# pi_pcb.net
KiCad netlist of a schematic drawn in EAGLE
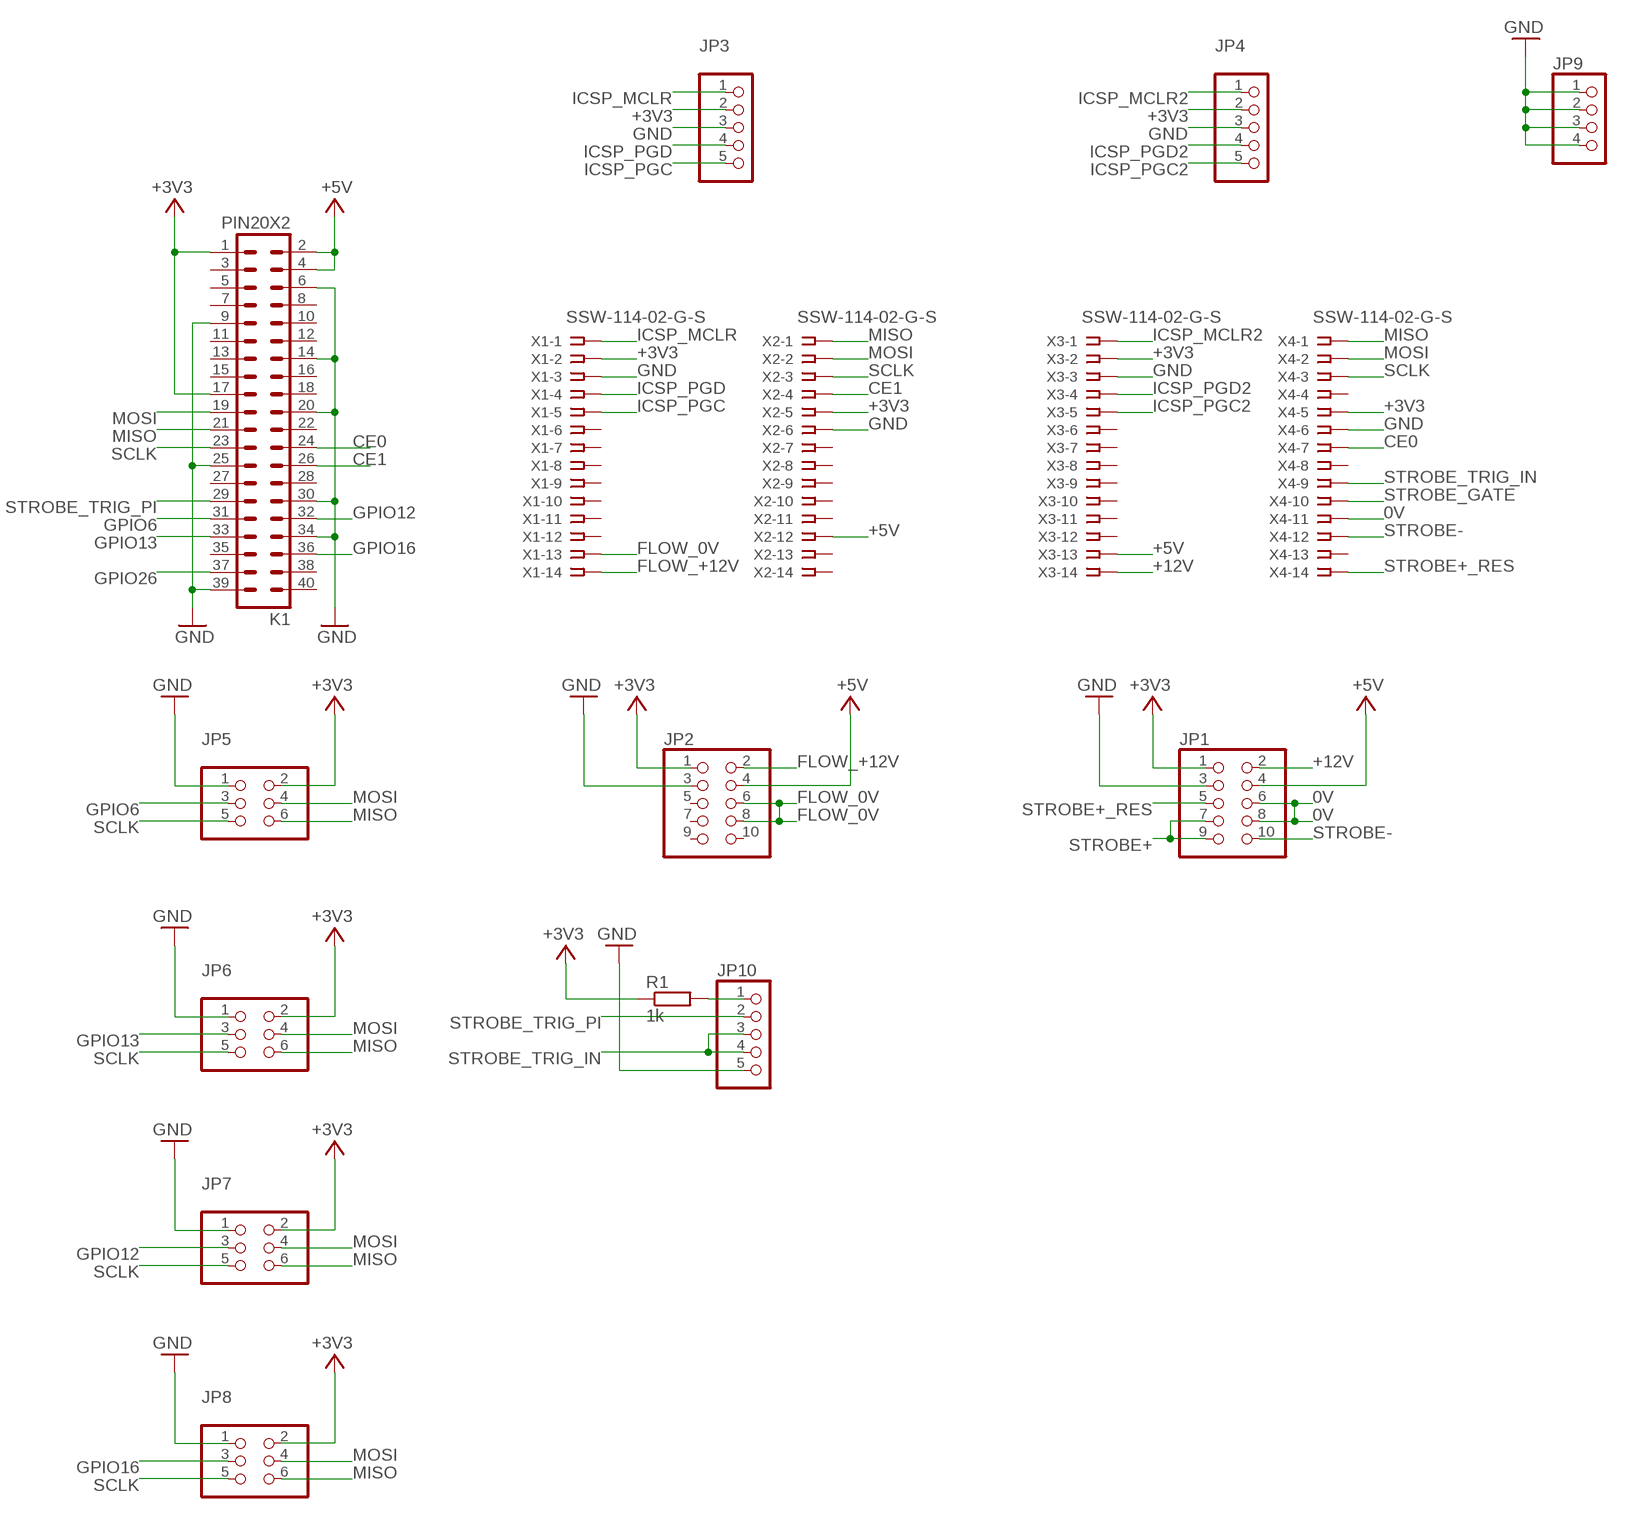
[diagram p0: schematic, sheet 1]

(export (version "E")
  (design (tool "Eeschema 10.0.6"))
  (components
    (comp (ref "JP1")
      (value "PINHD-2X5")
      (footprint "eagle-import:2X05")
      (libsource (lib "eagle-import") (part "PINHD-2X5"))
    )
    (comp (ref "JP2")
      (value "PINHD-2X5")
      (footprint "eagle-import:2X05")
      (libsource (lib "eagle-import") (part "PINHD-2X5"))
    )
    (comp (ref "JP3")
      (value "PINHD-1X5")
      (footprint "eagle-import:1X05")
      (libsource (lib "eagle-import") (part "PINHD-1X5"))
    )
    (comp (ref "JP4")
      (value "PINHD-1X5")
      (footprint "eagle-import:1X05")
      (libsource (lib "eagle-import") (part "PINHD-1X5"))
    )
    (comp (ref "JP5")
      (value "PINHD-2X3")
      (footprint "eagle-import:2X03")
      (libsource (lib "eagle-import") (part "PINHD-2X3"))
    )
    (comp (ref "JP6")
      (value "PINHD-2X3")
      (footprint "eagle-import:2X03")
      (libsource (lib "eagle-import") (part "PINHD-2X3"))
    )
    (comp (ref "JP7")
      (value "PINHD-2X3")
      (footprint "eagle-import:2X03")
      (libsource (lib "eagle-import") (part "PINHD-2X3"))
    )
    (comp (ref "JP8")
      (value "PINHD-2X3")
      (footprint "eagle-import:2X03")
      (libsource (lib "eagle-import") (part "PINHD-2X3"))
    )
    (comp (ref "JP9")
      (value "PINHD-1X4")
      (footprint "eagle-import:1X04")
      (libsource (lib "eagle-import") (part "PINHD-1X4"))
    )
    (comp (ref "JP10")
      (value "PINHD-1X5")
      (footprint "eagle-import:1X05")
      (libsource (lib "eagle-import") (part "PINHD-1X5"))
    )
    (comp (ref "K1")
      (value "PIN20X2")
      (footprint "eagle-import:PIN_20X2")
      (libsource (lib "eagle-import") (part "PIN20X2"))
    )
    (comp (ref "R1")
      (value "1k")
      (footprint "eagle-import:R1206")
      (libsource (lib "eagle-import") (part "R-EU_R1206"))
    )
    (comp (ref "X1")
      (value "SSW-114-02-G-S")
      (footprint "eagle-import:SSW-114-02-G-S")
      (fields (field (name "MF") "Samtec Inc."))
      (libsource (lib "eagle-import") (part "SSW-114-02-G-S"))
    )
    (comp (ref "X2")
      (value "SSW-114-02-G-S")
      (footprint "eagle-import:SSW-114-02-G-S")
      (fields (field (name "MF") "Samtec Inc."))
      (libsource (lib "eagle-import") (part "SSW-114-02-G-S"))
    )
    (comp (ref "X3")
      (value "SSW-114-02-G-S")
      (footprint "eagle-import:SSW-114-02-G-S")
      (fields (field (name "MF") "Samtec Inc."))
      (libsource (lib "eagle-import") (part "SSW-114-02-G-S"))
    )
    (comp (ref "X4")
      (value "SSW-114-02-G-S")
      (footprint "eagle-import:SSW-114-02-G-S")
      (fields (field (name "MF") "Samtec Inc."))
      (libsource (lib "eagle-import") (part "SSW-114-02-G-S"))
    )
  )
  (nets
    (net (code "1") (name "+3V3") (class "Default")
      (node (ref "JP1") (pin "1") (pinfunction "1_1") (pintype "passive"))
      (node (ref "JP2") (pin "1") (pinfunction "1_1") (pintype "passive"))
      (node (ref "JP3") (pin "2") (pinfunction "2_2") (pintype "passive"))
      (node (ref "JP4") (pin "2") (pinfunction "2_2") (pintype "passive"))
      (node (ref "JP5") (pin "2") (pinfunction "2_2") (pintype "passive"))
      (node (ref "JP6") (pin "2") (pinfunction "2_2") (pintype "passive"))
      (node (ref "JP7") (pin "2") (pinfunction "2_2") (pintype "passive"))
      (node (ref "JP8") (pin "2") (pinfunction "2_2") (pintype "passive"))
      (node (ref "K1") (pin "1") (pinfunction "1_1") (pintype "passive"))
      (node (ref "K1") (pin "17") (pinfunction "17_17") (pintype "passive"))
      (node (ref "R1") (pin "1") (pinfunction "1_1") (pintype "passive"))
      (node (ref "X1") (pin "2") (pinfunction "1_2") (pintype "passive"))
      (node (ref "X2") (pin "5") (pinfunction "1_5") (pintype "passive"))
      (node (ref "X3") (pin "2") (pinfunction "1_2") (pintype "passive"))
      (node (ref "X4") (pin "5") (pinfunction "1_5") (pintype "passive"))
    )
    (net (code "2") (name "+5V") (class "Default")
      (node (ref "JP1") (pin "4") (pinfunction "4_4") (pintype "passive"))
      (node (ref "JP2") (pin "4") (pinfunction "4_4") (pintype "passive"))
      (node (ref "K1") (pin "2") (pinfunction "2_2") (pintype "passive"))
      (node (ref "K1") (pin "4") (pinfunction "4_4") (pintype "passive"))
      (node (ref "X2") (pin "12") (pinfunction "1_12") (pintype "passive"))
      (node (ref "X3") (pin "13") (pinfunction "1_13") (pintype "passive"))
    )
    (net (code "3") (name "/+12V") (class "Default")
      (node (ref "JP1") (pin "2") (pinfunction "2_2") (pintype "passive"))
      (node (ref "X3") (pin "14") (pinfunction "1_14") (pintype "passive"))
    )
    (net (code "4") (name "/0V") (class "Default")
      (node (ref "JP1") (pin "6") (pinfunction "6_6") (pintype "passive"))
      (node (ref "JP1") (pin "8") (pinfunction "8_8") (pintype "passive"))
      (node (ref "X4") (pin "11") (pinfunction "1_11") (pintype "passive"))
    )
    (net (code "5") (name "/CE0") (class "Default")
      (node (ref "K1") (pin "24") (pinfunction "24_24") (pintype "passive"))
      (node (ref "X4") (pin "7") (pinfunction "1_7") (pintype "passive"))
    )
    (net (code "6") (name "/CE1") (class "Default")
      (node (ref "K1") (pin "26") (pinfunction "26_26") (pintype "passive"))
      (node (ref "X2") (pin "4") (pinfunction "1_4") (pintype "passive"))
    )
    (net (code "7") (name "/FLOW_+12V") (class "Default")
      (node (ref "JP2") (pin "2") (pinfunction "2_2") (pintype "passive"))
      (node (ref "X1") (pin "14") (pinfunction "1_14") (pintype "passive"))
    )
    (net (code "8") (name "/FLOW_0V") (class "Default")
      (node (ref "JP2") (pin "6") (pinfunction "6_6") (pintype "passive"))
      (node (ref "JP2") (pin "8") (pinfunction "8_8") (pintype "passive"))
      (node (ref "X1") (pin "13") (pinfunction "1_13") (pintype "passive"))
    )
    (net (code "9") (name "/GPIO6") (class "Default")
      (node (ref "JP5") (pin "3") (pinfunction "3_3") (pintype "passive"))
      (node (ref "K1") (pin "31") (pinfunction "31_31") (pintype "passive"))
    )
    (net (code "10") (name "/GPIO12") (class "Default")
      (node (ref "JP7") (pin "3") (pinfunction "3_3") (pintype "passive"))
      (node (ref "K1") (pin "32") (pinfunction "32_32") (pintype "passive"))
    )
    (net (code "11") (name "/GPIO13") (class "Default")
      (node (ref "JP6") (pin "3") (pinfunction "3_3") (pintype "passive"))
      (node (ref "K1") (pin "33") (pinfunction "33_33") (pintype "passive"))
    )
    (net (code "12") (name "/GPIO16") (class "Default")
      (node (ref "JP8") (pin "3") (pinfunction "3_3") (pintype "passive"))
      (node (ref "K1") (pin "36") (pinfunction "36_36") (pintype "passive"))
    )
    (net (code "13") (name "/GPIO26") (class "Default")
      (node (ref "K1") (pin "37") (pinfunction "37_37") (pintype "passive"))
    )
    (net (code "14") (name "/ICSP_MCLR") (class "Default")
      (node (ref "JP3") (pin "1") (pinfunction "1_1") (pintype "passive"))
      (node (ref "X1") (pin "1") (pinfunction "1_1") (pintype "passive"))
    )
    (net (code "15") (name "/ICSP_MCLR2") (class "Default")
      (node (ref "JP4") (pin "1") (pinfunction "1_1") (pintype "passive"))
      (node (ref "X3") (pin "1") (pinfunction "1_1") (pintype "passive"))
    )
    (net (code "16") (name "/ICSP_PGC") (class "Default")
      (node (ref "JP3") (pin "5") (pinfunction "5_5") (pintype "passive"))
      (node (ref "X1") (pin "5") (pinfunction "1_5") (pintype "passive"))
    )
    (net (code "17") (name "/ICSP_PGC2") (class "Default")
      (node (ref "JP4") (pin "5") (pinfunction "5_5") (pintype "passive"))
      (node (ref "X3") (pin "5") (pinfunction "1_5") (pintype "passive"))
    )
    (net (code "18") (name "/ICSP_PGD") (class "Default")
      (node (ref "JP3") (pin "4") (pinfunction "4_4") (pintype "passive"))
      (node (ref "X1") (pin "4") (pinfunction "1_4") (pintype "passive"))
    )
    (net (code "19") (name "/ICSP_PGD2") (class "Default")
      (node (ref "JP4") (pin "4") (pinfunction "4_4") (pintype "passive"))
      (node (ref "X3") (pin "4") (pinfunction "1_4") (pintype "passive"))
    )
    (net (code "20") (name "/MISO") (class "Default")
      (node (ref "JP5") (pin "6") (pinfunction "6_6") (pintype "passive"))
      (node (ref "JP6") (pin "6") (pinfunction "6_6") (pintype "passive"))
      (node (ref "JP7") (pin "6") (pinfunction "6_6") (pintype "passive"))
      (node (ref "JP8") (pin "6") (pinfunction "6_6") (pintype "passive"))
      (node (ref "K1") (pin "21") (pinfunction "21_21") (pintype "passive"))
      (node (ref "X2") (pin "1") (pinfunction "1_1") (pintype "passive"))
      (node (ref "X4") (pin "1") (pinfunction "1_1") (pintype "passive"))
    )
    (net (code "21") (name "/MOSI") (class "Default")
      (node (ref "JP5") (pin "4") (pinfunction "4_4") (pintype "passive"))
      (node (ref "JP6") (pin "4") (pinfunction "4_4") (pintype "passive"))
      (node (ref "JP7") (pin "4") (pinfunction "4_4") (pintype "passive"))
      (node (ref "JP8") (pin "4") (pinfunction "4_4") (pintype "passive"))
      (node (ref "K1") (pin "19") (pinfunction "19_19") (pintype "passive"))
      (node (ref "X2") (pin "2") (pinfunction "1_2") (pintype "passive"))
      (node (ref "X4") (pin "2") (pinfunction "1_2") (pintype "passive"))
    )
    (net (code "22") (name "/SCLK") (class "Default")
      (node (ref "JP5") (pin "5") (pinfunction "5_5") (pintype "passive"))
      (node (ref "JP6") (pin "5") (pinfunction "5_5") (pintype "passive"))
      (node (ref "JP7") (pin "5") (pinfunction "5_5") (pintype "passive"))
      (node (ref "JP8") (pin "5") (pinfunction "5_5") (pintype "passive"))
      (node (ref "K1") (pin "23") (pinfunction "23_23") (pintype "passive"))
      (node (ref "X2") (pin "3") (pinfunction "1_3") (pintype "passive"))
      (node (ref "X4") (pin "3") (pinfunction "1_3") (pintype "passive"))
    )
    (net (code "23") (name "/STROBE+") (class "Default")
      (node (ref "JP1") (pin "7") (pinfunction "7_7") (pintype "passive"))
      (node (ref "JP1") (pin "9") (pinfunction "9_9") (pintype "passive"))
    )
    (net (code "24") (name "/STROBE+_RES") (class "Default")
      (node (ref "JP1") (pin "5") (pinfunction "5_5") (pintype "passive"))
      (node (ref "X4") (pin "14") (pinfunction "1_14") (pintype "passive"))
    )
    (net (code "25") (name "/STROBE-") (class "Default")
      (node (ref "JP1") (pin "10") (pinfunction "10_10") (pintype "passive"))
      (node (ref "X4") (pin "12") (pinfunction "1_12") (pintype "passive"))
    )
    (net (code "26") (name "/STROBE_GATE") (class "Default")
      (node (ref "X4") (pin "10") (pinfunction "1_10") (pintype "passive"))
    )
    (net (code "27") (name "/STROBE_TRIG_IN") (class "Default")
      (node (ref "JP10") (pin "3") (pinfunction "3_3") (pintype "passive"))
      (node (ref "JP10") (pin "4") (pinfunction "4_4") (pintype "passive"))
      (node (ref "X4") (pin "9") (pinfunction "1_9") (pintype "passive"))
    )
    (net (code "28") (name "/STROBE_TRIG_PI") (class "Default")
      (node (ref "JP10") (pin "2") (pinfunction "2_2") (pintype "passive"))
      (node (ref "K1") (pin "29") (pinfunction "29_29") (pintype "passive"))
    )
    (net (code "29") (name "GND") (class "Default")
      (node (ref "JP1") (pin "3") (pinfunction "3_3") (pintype "passive"))
      (node (ref "JP10") (pin "5") (pinfunction "5_5") (pintype "passive"))
      (node (ref "JP2") (pin "3") (pinfunction "3_3") (pintype "passive"))
      (node (ref "JP3") (pin "3") (pinfunction "3_3") (pintype "passive"))
      (node (ref "JP4") (pin "3") (pinfunction "3_3") (pintype "passive"))
      (node (ref "JP5") (pin "1") (pinfunction "1_1") (pintype "passive"))
      (node (ref "JP6") (pin "1") (pinfunction "1_1") (pintype "passive"))
      (node (ref "JP7") (pin "1") (pinfunction "1_1") (pintype "passive"))
      (node (ref "JP8") (pin "1") (pinfunction "1_1") (pintype "passive"))
      (node (ref "JP9") (pin "1") (pinfunction "1_1") (pintype "passive"))
      (node (ref "JP9") (pin "2") (pinfunction "2_2") (pintype "passive"))
      (node (ref "JP9") (pin "3") (pinfunction "3_3") (pintype "passive"))
      (node (ref "JP9") (pin "4") (pinfunction "4_4") (pintype "passive"))
      (node (ref "K1") (pin "14") (pinfunction "14_14") (pintype "passive"))
      (node (ref "K1") (pin "20") (pinfunction "20_20") (pintype "passive"))
      (node (ref "K1") (pin "25") (pinfunction "25_25") (pintype "passive"))
      (node (ref "K1") (pin "30") (pinfunction "30_30") (pintype "passive"))
      (node (ref "K1") (pin "34") (pinfunction "34_34") (pintype "passive"))
      (node (ref "K1") (pin "39") (pinfunction "39_39") (pintype "passive"))
      (node (ref "K1") (pin "6") (pinfunction "6_6") (pintype "passive"))
      (node (ref "K1") (pin "9") (pinfunction "9_9") (pintype "passive"))
      (node (ref "X1") (pin "3") (pinfunction "1_3") (pintype "passive"))
      (node (ref "X2") (pin "6") (pinfunction "1_6") (pintype "passive"))
      (node (ref "X3") (pin "3") (pinfunction "1_3") (pintype "passive"))
      (node (ref "X4") (pin "6") (pinfunction "1_6") (pintype "passive"))
    )
    (net (code "30") (name "Net-(JP10-Pad1)") (class "Default")
      (node (ref "JP10") (pin "1") (pinfunction "1_1") (pintype "passive"))
      (node (ref "R1") (pin "2") (pinfunction "2_2") (pintype "passive"))
    )
    (net (code "31") (name "unconnected-(JP2-Pad5)") (class "Default")
      (node (ref "JP2") (pin "5") (pinfunction "5_5") (pintype "passive"))
    )
    (net (code "32") (name "unconnected-(JP2-Pad7)") (class "Default")
      (node (ref "JP2") (pin "7") (pinfunction "7_7") (pintype "passive"))
    )
    (net (code "33") (name "unconnected-(JP2-Pad9)") (class "Default")
      (node (ref "JP2") (pin "9") (pinfunction "9_9") (pintype "passive"))
    )
    (net (code "34") (name "unconnected-(JP2-Pad10)") (class "Default")
      (node (ref "JP2") (pin "10") (pinfunction "10_10") (pintype "passive"))
    )
    (net (code "35") (name "unconnected-(K1-Pad3)") (class "Default")
      (node (ref "K1") (pin "3") (pinfunction "3_3") (pintype "passive"))
    )
    (net (code "36") (name "unconnected-(K1-Pad5)") (class "Default")
      (node (ref "K1") (pin "5") (pinfunction "5_5") (pintype "passive"))
    )
    (net (code "37") (name "unconnected-(K1-Pad7)") (class "Default")
      (node (ref "K1") (pin "7") (pinfunction "7_7") (pintype "passive"))
    )
    (net (code "38") (name "unconnected-(K1-Pad8)") (class "Default")
      (node (ref "K1") (pin "8") (pinfunction "8_8") (pintype "passive"))
    )
    (net (code "39") (name "unconnected-(K1-Pad10)") (class "Default")
      (node (ref "K1") (pin "10") (pinfunction "10_10") (pintype "passive"))
    )
    (net (code "40") (name "unconnected-(K1-Pad11)") (class "Default")
      (node (ref "K1") (pin "11") (pinfunction "11_11") (pintype "passive"))
    )
    (net (code "41") (name "unconnected-(K1-Pad12)") (class "Default")
      (node (ref "K1") (pin "12") (pinfunction "12_12") (pintype "passive"))
    )
    (net (code "42") (name "unconnected-(K1-Pad13)") (class "Default")
      (node (ref "K1") (pin "13") (pinfunction "13_13") (pintype "passive"))
    )
    (net (code "43") (name "unconnected-(K1-Pad15)") (class "Default")
      (node (ref "K1") (pin "15") (pinfunction "15_15") (pintype "passive"))
    )
    (net (code "44") (name "unconnected-(K1-Pad16)") (class "Default")
      (node (ref "K1") (pin "16") (pinfunction "16_16") (pintype "passive"))
    )
    (net (code "45") (name "unconnected-(K1-Pad18)") (class "Default")
      (node (ref "K1") (pin "18") (pinfunction "18_18") (pintype "passive"))
    )
    (net (code "46") (name "unconnected-(K1-Pad22)") (class "Default")
      (node (ref "K1") (pin "22") (pinfunction "22_22") (pintype "passive"))
    )
    (net (code "47") (name "unconnected-(K1-Pad27)") (class "Default")
      (node (ref "K1") (pin "27") (pinfunction "27_27") (pintype "passive"))
    )
    (net (code "48") (name "unconnected-(K1-Pad28)") (class "Default")
      (node (ref "K1") (pin "28") (pinfunction "28_28") (pintype "passive"))
    )
    (net (code "49") (name "unconnected-(K1-Pad35)") (class "Default")
      (node (ref "K1") (pin "35") (pinfunction "35_35") (pintype "passive"))
    )
    (net (code "50") (name "unconnected-(K1-Pad38)") (class "Default")
      (node (ref "K1") (pin "38") (pinfunction "38_38") (pintype "passive"))
    )
    (net (code "51") (name "unconnected-(K1-Pad40)") (class "Default")
      (node (ref "K1") (pin "40") (pinfunction "40_40") (pintype "passive"))
    )
    (net (code "52") (name "unconnected-(X1B-1-Pad10)") (class "Default")
      (node (ref "X1") (pin "10") (pinfunction "1_10") (pintype "passive"))
    )
    (net (code "53") (name "unconnected-(X1C-1-Pad11)") (class "Default")
      (node (ref "X1") (pin "11") (pinfunction "1_11") (pintype "passive"))
    )
    (net (code "54") (name "unconnected-(X1D-1-Pad12)") (class "Default")
      (node (ref "X1") (pin "12") (pinfunction "1_12") (pintype "passive"))
    )
    (net (code "55") (name "unconnected-(X1K-1-Pad6)") (class "Default")
      (node (ref "X1") (pin "6") (pinfunction "1_6") (pintype "passive"))
    )
    (net (code "56") (name "unconnected-(X1L-1-Pad7)") (class "Default")
      (node (ref "X1") (pin "7") (pinfunction "1_7") (pintype "passive"))
    )
    (net (code "57") (name "unconnected-(X1M-1-Pad8)") (class "Default")
      (node (ref "X1") (pin "8") (pinfunction "1_8") (pintype "passive"))
    )
    (net (code "58") (name "unconnected-(X1N-1-Pad9)") (class "Default")
      (node (ref "X1") (pin "9") (pinfunction "1_9") (pintype "passive"))
    )
    (net (code "59") (name "unconnected-(X2B-1-Pad10)") (class "Default")
      (node (ref "X2") (pin "10") (pinfunction "1_10") (pintype "passive"))
    )
    (net (code "60") (name "unconnected-(X2C-1-Pad11)") (class "Default")
      (node (ref "X2") (pin "11") (pinfunction "1_11") (pintype "passive"))
    )
    (net (code "61") (name "unconnected-(X2E-1-Pad13)") (class "Default")
      (node (ref "X2") (pin "13") (pinfunction "1_13") (pintype "passive"))
    )
    (net (code "62") (name "unconnected-(X2F-1-Pad14)") (class "Default")
      (node (ref "X2") (pin "14") (pinfunction "1_14") (pintype "passive"))
    )
    (net (code "63") (name "unconnected-(X2L-1-Pad7)") (class "Default")
      (node (ref "X2") (pin "7") (pinfunction "1_7") (pintype "passive"))
    )
    (net (code "64") (name "unconnected-(X2M-1-Pad8)") (class "Default")
      (node (ref "X2") (pin "8") (pinfunction "1_8") (pintype "passive"))
    )
    (net (code "65") (name "unconnected-(X2N-1-Pad9)") (class "Default")
      (node (ref "X2") (pin "9") (pinfunction "1_9") (pintype "passive"))
    )
    (net (code "66") (name "unconnected-(X3B-1-Pad10)") (class "Default")
      (node (ref "X3") (pin "10") (pinfunction "1_10") (pintype "passive"))
    )
    (net (code "67") (name "unconnected-(X3C-1-Pad11)") (class "Default")
      (node (ref "X3") (pin "11") (pinfunction "1_11") (pintype "passive"))
    )
    (net (code "68") (name "unconnected-(X3D-1-Pad12)") (class "Default")
      (node (ref "X3") (pin "12") (pinfunction "1_12") (pintype "passive"))
    )
    (net (code "69") (name "unconnected-(X3K-1-Pad6)") (class "Default")
      (node (ref "X3") (pin "6") (pinfunction "1_6") (pintype "passive"))
    )
    (net (code "70") (name "unconnected-(X3L-1-Pad7)") (class "Default")
      (node (ref "X3") (pin "7") (pinfunction "1_7") (pintype "passive"))
    )
    (net (code "71") (name "unconnected-(X3M-1-Pad8)") (class "Default")
      (node (ref "X3") (pin "8") (pinfunction "1_8") (pintype "passive"))
    )
    (net (code "72") (name "unconnected-(X3N-1-Pad9)") (class "Default")
      (node (ref "X3") (pin "9") (pinfunction "1_9") (pintype "passive"))
    )
    (net (code "73") (name "unconnected-(X4E-1-Pad13)") (class "Default")
      (node (ref "X4") (pin "13") (pinfunction "1_13") (pintype "passive"))
    )
    (net (code "74") (name "unconnected-(X4I-1-Pad4)") (class "Default")
      (node (ref "X4") (pin "4") (pinfunction "1_4") (pintype "passive"))
    )
    (net (code "75") (name "unconnected-(X4M-1-Pad8)") (class "Default")
      (node (ref "X4") (pin "8") (pinfunction "1_8") (pintype "passive"))
    )
  )
)
